# Digits.net
KiCad netlist of a schematic drawn in Altium Designer
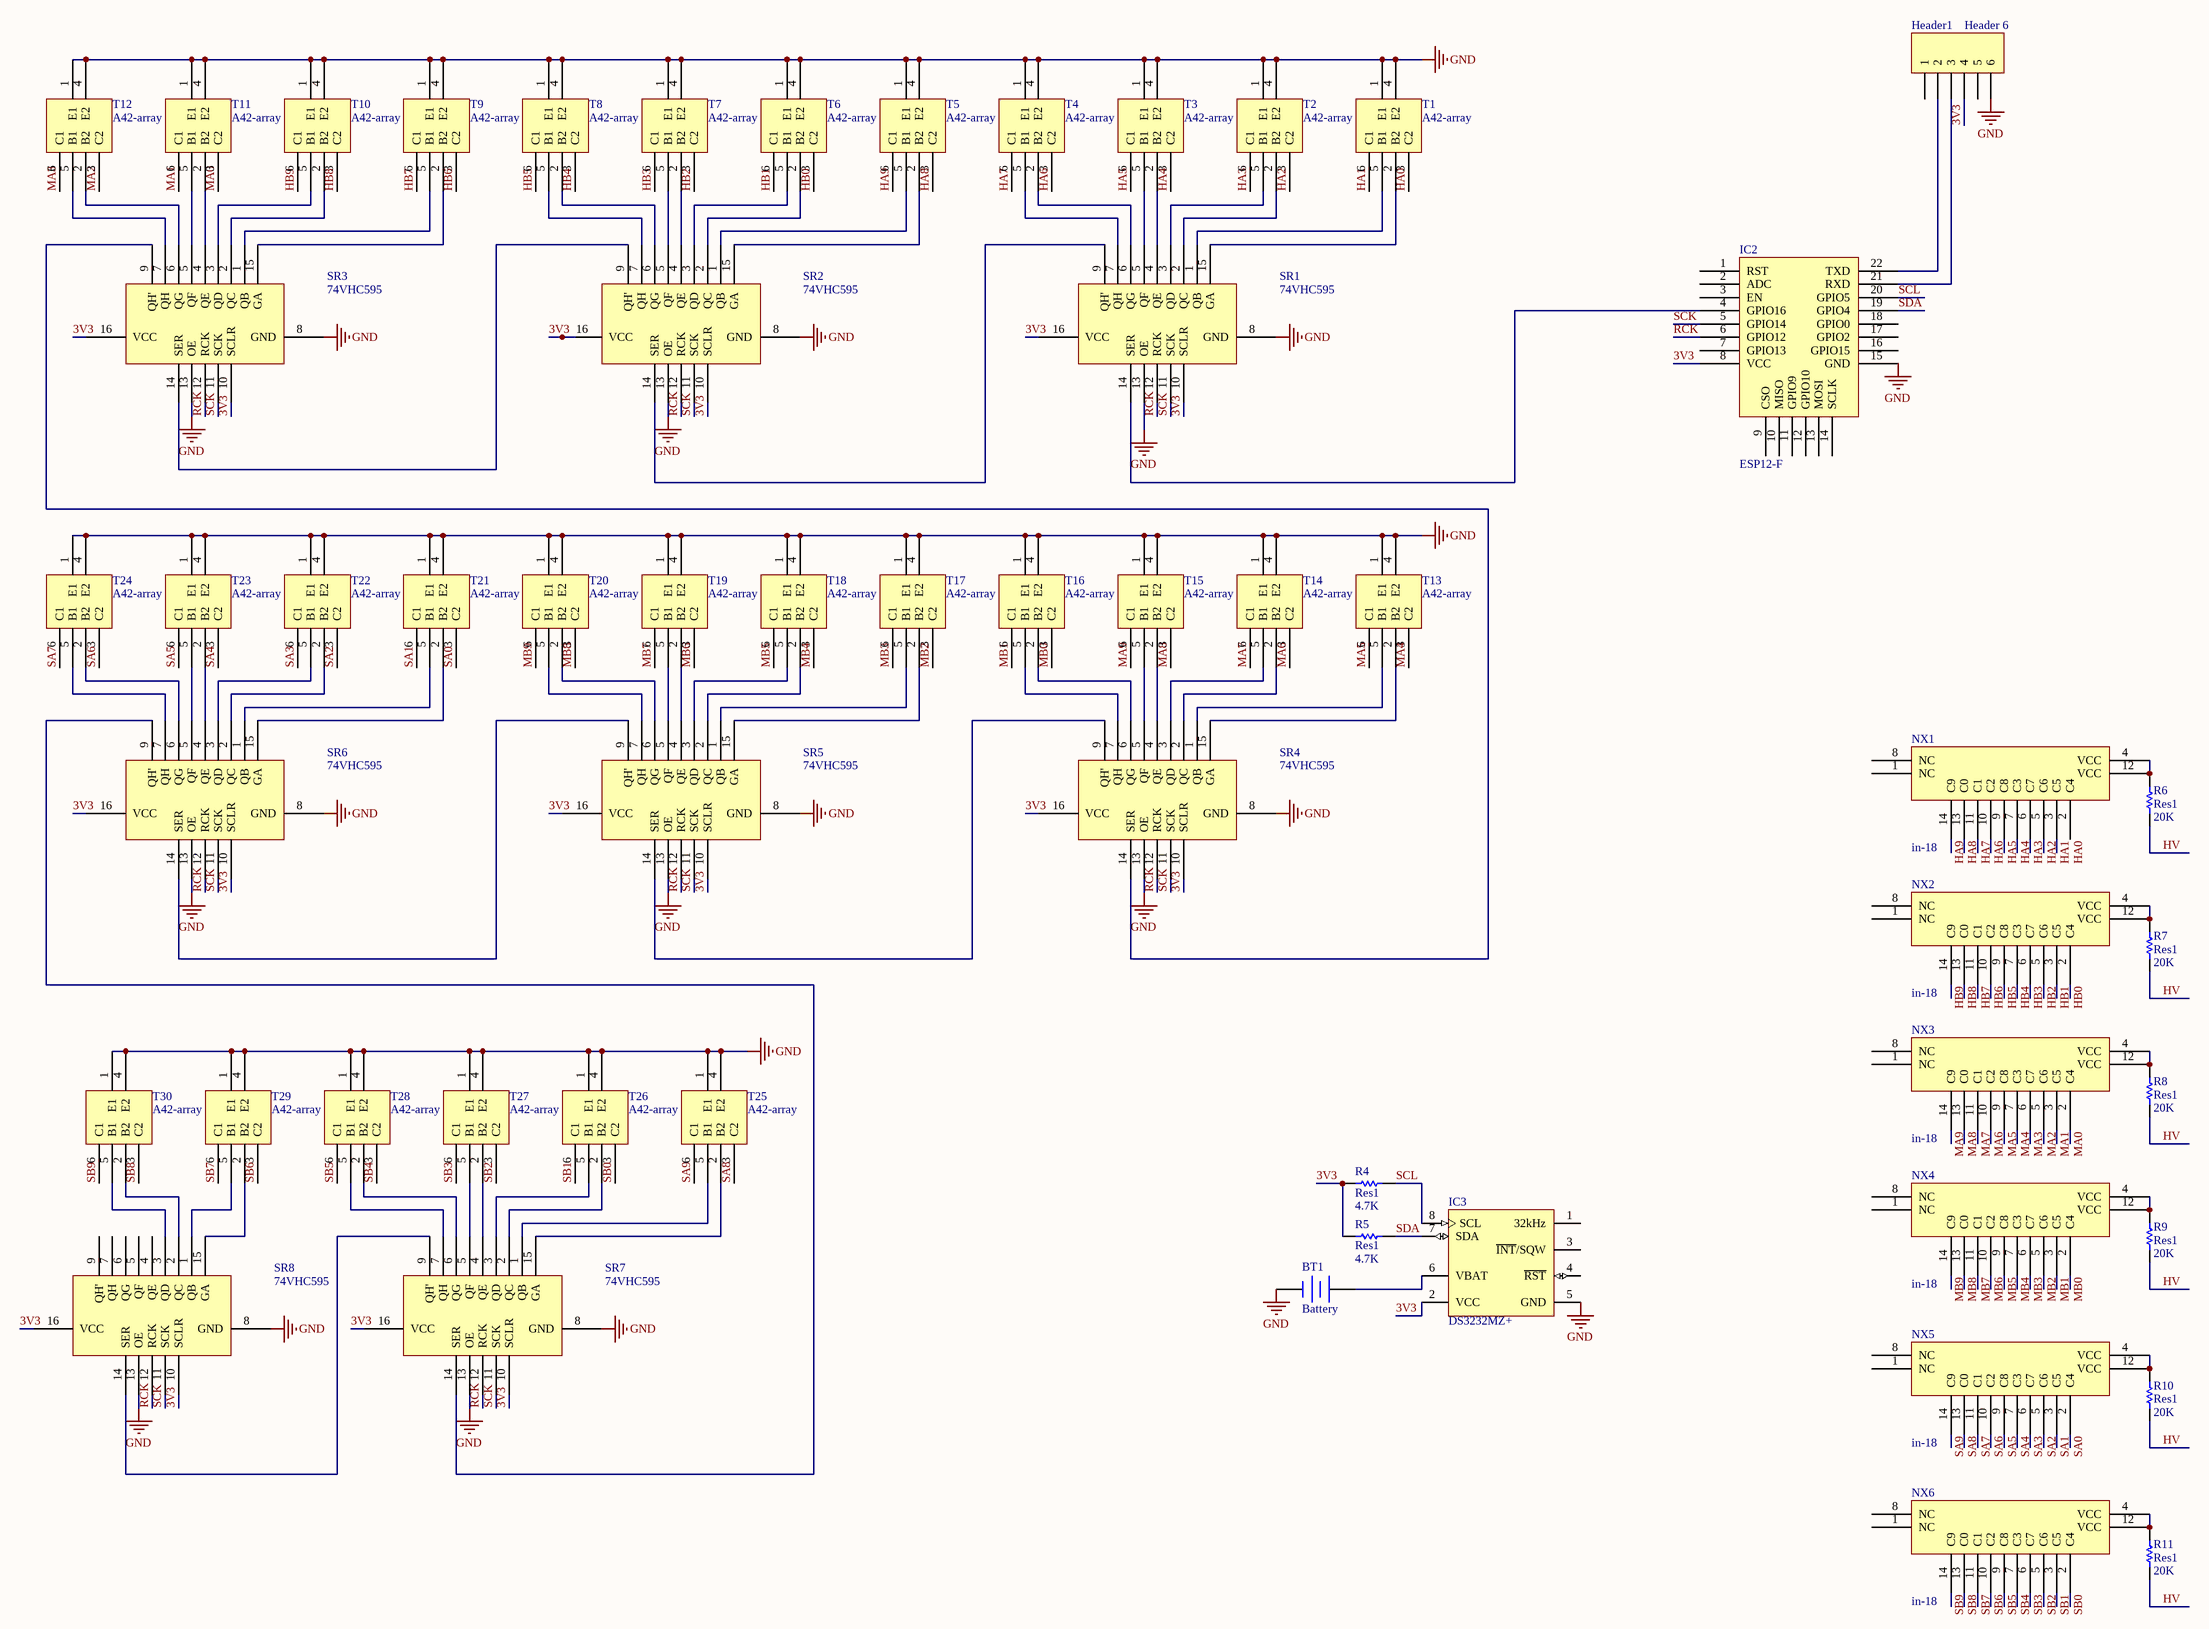
[diagram p0: Digits.SchDoc]

(export (version "E")
  (design (tool "Eeschema 10.0.6"))
  (components
    (comp (ref "BT1")
      (value "Battery")
      (footprint "cr1220")
      (description "Multicell Battery")
      (fields (field (name "PUBLISHER") "Altium Limited"))
      (libsource (lib "Miscellaneous Devices") (part "Battery"))
    )
    (comp (ref "Header1")
      (value "Header 6")
      (footprint "HDR1X6")
      (description "Header, 6-Pin")
      (fields (field (name "PUBLISHER") "Altium Limited"))
      (libsource (lib "Miscellaneous Connectors") (part "Header 6"))
    )
    (comp (ref "IC2")
      (value "ESP12-F")
      (footprint "ESP12-F")
      (libsource (lib "CustomComponentsLibrary") (part "ESP12-F"))
    )
    (comp (ref "IC3")
      (value "DS3232MZ+")
      (footprint "DS3231")
      (libsource (lib "Maxim Real-Time Clocks (RTCs)") (part "DS3232MZ+"))
    )
    (comp (ref "NX1")
      (value "in-18")
      (footprint "in-18")
      (libsource (lib "CustomComponentsLibrary") (part "in-18"))
    )
    (comp (ref "NX2")
      (value "in-18")
      (footprint "in-18")
      (libsource (lib "CustomComponentsLibrary") (part "in-18"))
    )
    (comp (ref "NX3")
      (value "in-18")
      (footprint "in-18")
      (libsource (lib "CustomComponentsLibrary") (part "in-18"))
    )
    (comp (ref "NX4")
      (value "in-18")
      (footprint "in-18")
      (libsource (lib "CustomComponentsLibrary") (part "in-18"))
    )
    (comp (ref "NX5")
      (value "in-18")
      (footprint "in-18")
      (libsource (lib "CustomComponentsLibrary") (part "in-18"))
    )
    (comp (ref "NX6")
      (value "in-18")
      (footprint "in-18")
      (libsource (lib "CustomComponentsLibrary") (part "in-18"))
    )
    (comp (ref "R4")
      (value "Res1")
      (footprint "6-0805_M")
      (description "Resistor")
      (fields (field (name "ALTIUM_VALUE") "4.7K") (field (name "PUBLISHER") "Altium Limited"))
      (libsource (lib "Miscellaneous Devices") (part "Res1"))
    )
    (comp (ref "R5")
      (value "Res1")
      (footprint "6-0805_M")
      (description "Resistor")
      (fields (field (name "ALTIUM_VALUE") "4.7K") (field (name "PUBLISHER") "Altium Limited"))
      (libsource (lib "Miscellaneous Devices") (part "Res1"))
    )
    (comp (ref "R6")
      (value "Res1")
      (footprint "6-0805_M")
      (description "Resistor")
      (fields (field (name "ALTIUM_VALUE") "20K") (field (name "PUBLISHER") "Altium Limited"))
      (libsource (lib "Miscellaneous Devices") (part "Res1"))
    )
    (comp (ref "R7")
      (value "Res1")
      (footprint "6-0805_M")
      (description "Resistor")
      (fields (field (name "ALTIUM_VALUE") "20K") (field (name "PUBLISHER") "Altium Limited"))
      (libsource (lib "Miscellaneous Devices") (part "Res1"))
    )
    (comp (ref "R8")
      (value "Res1")
      (footprint "6-0805_M")
      (description "Resistor")
      (fields (field (name "ALTIUM_VALUE") "20K") (field (name "PUBLISHER") "Altium Limited"))
      (libsource (lib "Miscellaneous Devices") (part "Res1"))
    )
    (comp (ref "R9")
      (value "Res1")
      (footprint "6-0805_M")
      (description "Resistor")
      (fields (field (name "ALTIUM_VALUE") "20K") (field (name "PUBLISHER") "Altium Limited"))
      (libsource (lib "Miscellaneous Devices") (part "Res1"))
    )
    (comp (ref "R10")
      (value "Res1")
      (footprint "6-0805_M")
      (description "Resistor")
      (fields (field (name "ALTIUM_VALUE") "20K") (field (name "PUBLISHER") "Altium Limited"))
      (libsource (lib "Miscellaneous Devices") (part "Res1"))
    )
    (comp (ref "R11")
      (value "Res1")
      (footprint "6-0805_M")
      (description "Resistor")
      (fields (field (name "ALTIUM_VALUE") "20K") (field (name "PUBLISHER") "Altium Limited"))
      (libsource (lib "Miscellaneous Devices") (part "Res1"))
    )
    (comp (ref "SR1")
      (value "74VHC595")
      (footprint "74VHC595")
      (libsource (lib "CustomComponentsLibrary") (part "74VHC595"))
    )
    (comp (ref "SR2")
      (value "74VHC595")
      (footprint "74VHC595")
      (libsource (lib "CustomComponentsLibrary") (part "74VHC595"))
    )
    (comp (ref "SR3")
      (value "74VHC595")
      (footprint "74VHC595")
      (libsource (lib "CustomComponentsLibrary") (part "74VHC595"))
    )
    (comp (ref "SR4")
      (value "74VHC595")
      (footprint "74VHC595")
      (libsource (lib "CustomComponentsLibrary") (part "74VHC595"))
    )
    (comp (ref "SR5")
      (value "74VHC595")
      (footprint "74VHC595")
      (libsource (lib "CustomComponentsLibrary") (part "74VHC595"))
    )
    (comp (ref "SR6")
      (value "74VHC595")
      (footprint "74VHC595")
      (libsource (lib "CustomComponentsLibrary") (part "74VHC595"))
    )
    (comp (ref "SR7")
      (value "74VHC595")
      (footprint "74VHC595")
      (libsource (lib "CustomComponentsLibrary") (part "74VHC595"))
    )
    (comp (ref "SR8")
      (value "74VHC595")
      (footprint "74VHC595")
      (libsource (lib "CustomComponentsLibrary") (part "74VHC595"))
    )
    (comp (ref "T1")
      (value "A42-array")
      (footprint "SOT457")
      (libsource (lib "CustomComponentsLibrary") (part "A42-array"))
    )
    (comp (ref "T2")
      (value "A42-array")
      (footprint "SOT457")
      (libsource (lib "CustomComponentsLibrary") (part "A42-array"))
    )
    (comp (ref "T3")
      (value "A42-array")
      (footprint "SOT457")
      (libsource (lib "CustomComponentsLibrary") (part "A42-array"))
    )
    (comp (ref "T4")
      (value "A42-array")
      (footprint "SOT457")
      (libsource (lib "CustomComponentsLibrary") (part "A42-array"))
    )
    (comp (ref "T5")
      (value "A42-array")
      (footprint "SOT457")
      (libsource (lib "CustomComponentsLibrary") (part "A42-array"))
    )
    (comp (ref "T6")
      (value "A42-array")
      (footprint "SOT457")
      (libsource (lib "CustomComponentsLibrary") (part "A42-array"))
    )
    (comp (ref "T7")
      (value "A42-array")
      (footprint "SOT457")
      (libsource (lib "CustomComponentsLibrary") (part "A42-array"))
    )
    (comp (ref "T8")
      (value "A42-array")
      (footprint "SOT457")
      (libsource (lib "CustomComponentsLibrary") (part "A42-array"))
    )
    (comp (ref "T9")
      (value "A42-array")
      (footprint "SOT457")
      (libsource (lib "CustomComponentsLibrary") (part "A42-array"))
    )
    (comp (ref "T10")
      (value "A42-array")
      (footprint "SOT457")
      (libsource (lib "CustomComponentsLibrary") (part "A42-array"))
    )
    (comp (ref "T11")
      (value "A42-array")
      (footprint "SOT457")
      (libsource (lib "CustomComponentsLibrary") (part "A42-array"))
    )
    (comp (ref "T12")
      (value "A42-array")
      (footprint "SOT457")
      (libsource (lib "CustomComponentsLibrary") (part "A42-array"))
    )
    (comp (ref "T13")
      (value "A42-array")
      (footprint "SOT457")
      (libsource (lib "CustomComponentsLibrary") (part "A42-array"))
    )
    (comp (ref "T14")
      (value "A42-array")
      (footprint "SOT457")
      (libsource (lib "CustomComponentsLibrary") (part "A42-array"))
    )
    (comp (ref "T15")
      (value "A42-array")
      (footprint "SOT457")
      (libsource (lib "CustomComponentsLibrary") (part "A42-array"))
    )
    (comp (ref "T16")
      (value "A42-array")
      (footprint "SOT457")
      (libsource (lib "CustomComponentsLibrary") (part "A42-array"))
    )
    (comp (ref "T17")
      (value "A42-array")
      (footprint "SOT457")
      (libsource (lib "CustomComponentsLibrary") (part "A42-array"))
    )
    (comp (ref "T18")
      (value "A42-array")
      (footprint "SOT457")
      (libsource (lib "CustomComponentsLibrary") (part "A42-array"))
    )
    (comp (ref "T19")
      (value "A42-array")
      (footprint "SOT457")
      (libsource (lib "CustomComponentsLibrary") (part "A42-array"))
    )
    (comp (ref "T20")
      (value "A42-array")
      (footprint "SOT457")
      (libsource (lib "CustomComponentsLibrary") (part "A42-array"))
    )
    (comp (ref "T21")
      (value "A42-array")
      (footprint "SOT457")
      (libsource (lib "CustomComponentsLibrary") (part "A42-array"))
    )
    (comp (ref "T22")
      (value "A42-array")
      (footprint "SOT457")
      (libsource (lib "CustomComponentsLibrary") (part "A42-array"))
    )
    (comp (ref "T23")
      (value "A42-array")
      (footprint "SOT457")
      (libsource (lib "CustomComponentsLibrary") (part "A42-array"))
    )
    (comp (ref "T24")
      (value "A42-array")
      (footprint "SOT457")
      (libsource (lib "CustomComponentsLibrary") (part "A42-array"))
    )
    (comp (ref "T25")
      (value "A42-array")
      (footprint "SOT457")
      (libsource (lib "CustomComponentsLibrary") (part "A42-array"))
    )
    (comp (ref "T26")
      (value "A42-array")
      (footprint "SOT457")
      (libsource (lib "CustomComponentsLibrary") (part "A42-array"))
    )
    (comp (ref "T27")
      (value "A42-array")
      (footprint "SOT457")
      (libsource (lib "CustomComponentsLibrary") (part "A42-array"))
    )
    (comp (ref "T28")
      (value "A42-array")
      (footprint "SOT457")
      (libsource (lib "CustomComponentsLibrary") (part "A42-array"))
    )
    (comp (ref "T29")
      (value "A42-array")
      (footprint "SOT457")
      (libsource (lib "CustomComponentsLibrary") (part "A42-array"))
    )
    (comp (ref "T30")
      (value "A42-array")
      (footprint "SOT457")
      (libsource (lib "CustomComponentsLibrary") (part "A42-array"))
    )
  )
  (nets
    (net (code "1") (name "/3V3") (class "Default")
      (node (ref "Header1") (pin "4") (pinfunction "4_4") (pintype "passive"))
      (node (ref "IC2") (pin "8") (pinfunction "VCC_8") (pintype "passive"))
      (node (ref "IC3") (pin "2") (pinfunction "VCC_2") (pintype "power_in"))
      (node (ref "R4") (pin "2") (pinfunction "2_2") (pintype "passive"))
      (node (ref "R5") (pin "2") (pinfunction "2_2") (pintype "passive"))
      (node (ref "SR1") (pin "10") (pinfunction "SCLR_10") (pintype "passive"))
      (node (ref "SR1") (pin "16") (pinfunction "VCC_16") (pintype "passive"))
      (node (ref "SR2") (pin "10") (pinfunction "SCLR_10") (pintype "passive"))
      (node (ref "SR2") (pin "16") (pinfunction "VCC_16") (pintype "passive"))
      (node (ref "SR3") (pin "10") (pinfunction "SCLR_10") (pintype "passive"))
      (node (ref "SR3") (pin "16") (pinfunction "VCC_16") (pintype "passive"))
      (node (ref "SR4") (pin "10") (pinfunction "SCLR_10") (pintype "passive"))
      (node (ref "SR4") (pin "16") (pinfunction "VCC_16") (pintype "passive"))
      (node (ref "SR5") (pin "10") (pinfunction "SCLR_10") (pintype "passive"))
      (node (ref "SR5") (pin "16") (pinfunction "VCC_16") (pintype "passive"))
      (node (ref "SR6") (pin "10") (pinfunction "SCLR_10") (pintype "passive"))
      (node (ref "SR6") (pin "16") (pinfunction "VCC_16") (pintype "passive"))
      (node (ref "SR7") (pin "10") (pinfunction "SCLR_10") (pintype "passive"))
      (node (ref "SR7") (pin "16") (pinfunction "VCC_16") (pintype "passive"))
      (node (ref "SR8") (pin "10") (pinfunction "SCLR_10") (pintype "passive"))
      (node (ref "SR8") (pin "16") (pinfunction "VCC_16") (pintype "passive"))
    )
    (net (code "2") (name "/HA0") (class "Default")
      (node (ref "NX1") (pin "2") (pinfunction "C4_2") (pintype "passive"))
      (node (ref "T1") (pin "3") (pinfunction "C2_3") (pintype "passive"))
    )
    (net (code "3") (name "/HA1") (class "Default")
      (node (ref "NX1") (pin "3") (pinfunction "C5_3") (pintype "passive"))
      (node (ref "T1") (pin "6") (pinfunction "C1_6") (pintype "passive"))
    )
    (net (code "4") (name "/HA2") (class "Default")
      (node (ref "NX1") (pin "5") (pinfunction "C6_5") (pintype "passive"))
      (node (ref "T2") (pin "3") (pinfunction "C2_3") (pintype "passive"))
    )
    (net (code "5") (name "/HA3") (class "Default")
      (node (ref "NX1") (pin "6") (pinfunction "C7_6") (pintype "passive"))
      (node (ref "T2") (pin "6") (pinfunction "C1_6") (pintype "passive"))
    )
    (net (code "6") (name "/HA4") (class "Default")
      (node (ref "NX1") (pin "7") (pinfunction "C3_7") (pintype "passive"))
      (node (ref "T3") (pin "3") (pinfunction "C2_3") (pintype "passive"))
    )
    (net (code "7") (name "/HA5") (class "Default")
      (node (ref "NX1") (pin "9") (pinfunction "C8_9") (pintype "passive"))
      (node (ref "T3") (pin "6") (pinfunction "C1_6") (pintype "passive"))
    )
    (net (code "8") (name "/HA6") (class "Default")
      (node (ref "NX1") (pin "10") (pinfunction "C2_10") (pintype "passive"))
      (node (ref "T4") (pin "3") (pinfunction "C2_3") (pintype "passive"))
    )
    (net (code "9") (name "/HA7") (class "Default")
      (node (ref "NX1") (pin "11") (pinfunction "C1_11") (pintype "passive"))
      (node (ref "T4") (pin "6") (pinfunction "C1_6") (pintype "passive"))
    )
    (net (code "10") (name "/HA8") (class "Default")
      (node (ref "NX1") (pin "13") (pinfunction "C0_13") (pintype "passive"))
      (node (ref "T5") (pin "3") (pinfunction "C2_3") (pintype "passive"))
    )
    (net (code "11") (name "/HA9") (class "Default")
      (node (ref "NX1") (pin "14") (pinfunction "C9_14") (pintype "passive"))
      (node (ref "T5") (pin "6") (pinfunction "C1_6") (pintype "passive"))
    )
    (net (code "12") (name "/HB0") (class "Default")
      (node (ref "NX2") (pin "2") (pinfunction "C4_2") (pintype "passive"))
      (node (ref "T6") (pin "3") (pinfunction "C2_3") (pintype "passive"))
    )
    (net (code "13") (name "/HB1") (class "Default")
      (node (ref "NX2") (pin "3") (pinfunction "C5_3") (pintype "passive"))
      (node (ref "T6") (pin "6") (pinfunction "C1_6") (pintype "passive"))
    )
    (net (code "14") (name "/HB2") (class "Default")
      (node (ref "NX2") (pin "5") (pinfunction "C6_5") (pintype "passive"))
      (node (ref "T7") (pin "3") (pinfunction "C2_3") (pintype "passive"))
    )
    (net (code "15") (name "/HB3") (class "Default")
      (node (ref "NX2") (pin "6") (pinfunction "C7_6") (pintype "passive"))
      (node (ref "T7") (pin "6") (pinfunction "C1_6") (pintype "passive"))
    )
    (net (code "16") (name "/HB4") (class "Default")
      (node (ref "NX2") (pin "7") (pinfunction "C3_7") (pintype "passive"))
      (node (ref "T8") (pin "3") (pinfunction "C2_3") (pintype "passive"))
    )
    (net (code "17") (name "/HB5") (class "Default")
      (node (ref "NX2") (pin "9") (pinfunction "C8_9") (pintype "passive"))
      (node (ref "T8") (pin "6") (pinfunction "C1_6") (pintype "passive"))
    )
    (net (code "18") (name "/HB6") (class "Default")
      (node (ref "NX2") (pin "10") (pinfunction "C2_10") (pintype "passive"))
      (node (ref "T9") (pin "3") (pinfunction "C2_3") (pintype "passive"))
    )
    (net (code "19") (name "/HB7") (class "Default")
      (node (ref "NX2") (pin "11") (pinfunction "C1_11") (pintype "passive"))
      (node (ref "T9") (pin "6") (pinfunction "C1_6") (pintype "passive"))
    )
    (net (code "20") (name "/HB8") (class "Default")
      (node (ref "NX2") (pin "13") (pinfunction "C0_13") (pintype "passive"))
      (node (ref "T10") (pin "3") (pinfunction "C2_3") (pintype "passive"))
    )
    (net (code "21") (name "/HB9") (class "Default")
      (node (ref "NX2") (pin "14") (pinfunction "C9_14") (pintype "passive"))
      (node (ref "T10") (pin "6") (pinfunction "C1_6") (pintype "passive"))
    )
    (net (code "22") (name "/HV") (class "Default")
      (node (ref "R10") (pin "1") (pinfunction "1_1") (pintype "passive"))
      (node (ref "R11") (pin "1") (pinfunction "1_1") (pintype "passive"))
      (node (ref "R6") (pin "1") (pinfunction "1_1") (pintype "passive"))
      (node (ref "R7") (pin "1") (pinfunction "1_1") (pintype "passive"))
      (node (ref "R8") (pin "1") (pinfunction "1_1") (pintype "passive"))
      (node (ref "R9") (pin "1") (pinfunction "1_1") (pintype "passive"))
    )
    (net (code "23") (name "/MA0") (class "Default")
      (node (ref "NX3") (pin "2") (pinfunction "C4_2") (pintype "passive"))
      (node (ref "T11") (pin "3") (pinfunction "C2_3") (pintype "passive"))
    )
    (net (code "24") (name "/MA1") (class "Default")
      (node (ref "NX3") (pin "3") (pinfunction "C5_3") (pintype "passive"))
      (node (ref "T11") (pin "6") (pinfunction "C1_6") (pintype "passive"))
    )
    (net (code "25") (name "/MA2") (class "Default")
      (node (ref "NX3") (pin "5") (pinfunction "C6_5") (pintype "passive"))
      (node (ref "T12") (pin "3") (pinfunction "C2_3") (pintype "passive"))
    )
    (net (code "26") (name "/MA3") (class "Default")
      (node (ref "NX3") (pin "6") (pinfunction "C7_6") (pintype "passive"))
      (node (ref "T12") (pin "6") (pinfunction "C1_6") (pintype "passive"))
    )
    (net (code "27") (name "/MA4") (class "Default")
      (node (ref "NX3") (pin "7") (pinfunction "C3_7") (pintype "passive"))
      (node (ref "T13") (pin "3") (pinfunction "C2_3") (pintype "passive"))
    )
    (net (code "28") (name "/MA5") (class "Default")
      (node (ref "NX3") (pin "9") (pinfunction "C8_9") (pintype "passive"))
      (node (ref "T13") (pin "6") (pinfunction "C1_6") (pintype "passive"))
    )
    (net (code "29") (name "/MA6") (class "Default")
      (node (ref "NX3") (pin "10") (pinfunction "C2_10") (pintype "passive"))
      (node (ref "T14") (pin "3") (pinfunction "C2_3") (pintype "passive"))
    )
    (net (code "30") (name "/MA7") (class "Default")
      (node (ref "NX3") (pin "11") (pinfunction "C1_11") (pintype "passive"))
      (node (ref "T14") (pin "6") (pinfunction "C1_6") (pintype "passive"))
    )
    (net (code "31") (name "/MA8") (class "Default")
      (node (ref "NX3") (pin "13") (pinfunction "C0_13") (pintype "passive"))
      (node (ref "T15") (pin "3") (pinfunction "C2_3") (pintype "passive"))
    )
    (net (code "32") (name "/MA9") (class "Default")
      (node (ref "NX3") (pin "14") (pinfunction "C9_14") (pintype "passive"))
      (node (ref "T15") (pin "6") (pinfunction "C1_6") (pintype "passive"))
    )
    (net (code "33") (name "/MB0") (class "Default")
      (node (ref "NX4") (pin "2") (pinfunction "C4_2") (pintype "passive"))
      (node (ref "T16") (pin "3") (pinfunction "C2_3") (pintype "passive"))
    )
    (net (code "34") (name "/MB1") (class "Default")
      (node (ref "NX4") (pin "3") (pinfunction "C5_3") (pintype "passive"))
      (node (ref "T16") (pin "6") (pinfunction "C1_6") (pintype "passive"))
    )
    (net (code "35") (name "/MB2") (class "Default")
      (node (ref "NX4") (pin "5") (pinfunction "C6_5") (pintype "passive"))
      (node (ref "T17") (pin "3") (pinfunction "C2_3") (pintype "passive"))
    )
    (net (code "36") (name "/MB3") (class "Default")
      (node (ref "NX4") (pin "6") (pinfunction "C7_6") (pintype "passive"))
      (node (ref "T17") (pin "6") (pinfunction "C1_6") (pintype "passive"))
    )
    (net (code "37") (name "/MB4") (class "Default")
      (node (ref "NX4") (pin "7") (pinfunction "C3_7") (pintype "passive"))
      (node (ref "T18") (pin "3") (pinfunction "C2_3") (pintype "passive"))
    )
    (net (code "38") (name "/MB5") (class "Default")
      (node (ref "NX4") (pin "9") (pinfunction "C8_9") (pintype "passive"))
      (node (ref "T18") (pin "6") (pinfunction "C1_6") (pintype "passive"))
    )
    (net (code "39") (name "/MB6") (class "Default")
      (node (ref "NX4") (pin "10") (pinfunction "C2_10") (pintype "passive"))
      (node (ref "T19") (pin "3") (pinfunction "C2_3") (pintype "passive"))
    )
    (net (code "40") (name "/MB7") (class "Default")
      (node (ref "NX4") (pin "11") (pinfunction "C1_11") (pintype "passive"))
      (node (ref "T19") (pin "6") (pinfunction "C1_6") (pintype "passive"))
    )
    (net (code "41") (name "/MB8") (class "Default")
      (node (ref "NX4") (pin "13") (pinfunction "C0_13") (pintype "passive"))
      (node (ref "T20") (pin "3") (pinfunction "C2_3") (pintype "passive"))
    )
    (net (code "42") (name "/MB9") (class "Default")
      (node (ref "NX4") (pin "14") (pinfunction "C9_14") (pintype "passive"))
      (node (ref "T20") (pin "6") (pinfunction "C1_6") (pintype "passive"))
    )
    (net (code "43") (name "/RCK") (class "Default")
      (node (ref "IC2") (pin "6") (pinfunction "GPIO12_6") (pintype "passive"))
      (node (ref "SR1") (pin "12") (pinfunction "RCK_12") (pintype "passive"))
      (node (ref "SR2") (pin "12") (pinfunction "RCK_12") (pintype "passive"))
      (node (ref "SR3") (pin "12") (pinfunction "RCK_12") (pintype "passive"))
      (node (ref "SR4") (pin "12") (pinfunction "RCK_12") (pintype "passive"))
      (node (ref "SR5") (pin "12") (pinfunction "RCK_12") (pintype "passive"))
      (node (ref "SR6") (pin "12") (pinfunction "RCK_12") (pintype "passive"))
      (node (ref "SR7") (pin "12") (pinfunction "RCK_12") (pintype "passive"))
      (node (ref "SR8") (pin "12") (pinfunction "RCK_12") (pintype "passive"))
    )
    (net (code "44") (name "/SA0") (class "Default")
      (node (ref "NX5") (pin "2") (pinfunction "C4_2") (pintype "passive"))
      (node (ref "T21") (pin "3") (pinfunction "C2_3") (pintype "passive"))
    )
    (net (code "45") (name "/SA1") (class "Default")
      (node (ref "NX5") (pin "3") (pinfunction "C5_3") (pintype "passive"))
      (node (ref "T21") (pin "6") (pinfunction "C1_6") (pintype "passive"))
    )
    (net (code "46") (name "/SA2") (class "Default")
      (node (ref "NX5") (pin "5") (pinfunction "C6_5") (pintype "passive"))
      (node (ref "T22") (pin "3") (pinfunction "C2_3") (pintype "passive"))
    )
    (net (code "47") (name "/SA3") (class "Default")
      (node (ref "NX5") (pin "6") (pinfunction "C7_6") (pintype "passive"))
      (node (ref "T22") (pin "6") (pinfunction "C1_6") (pintype "passive"))
    )
    (net (code "48") (name "/SA4") (class "Default")
      (node (ref "NX5") (pin "7") (pinfunction "C3_7") (pintype "passive"))
      (node (ref "T23") (pin "3") (pinfunction "C2_3") (pintype "passive"))
    )
    (net (code "49") (name "/SA5") (class "Default")
      (node (ref "NX5") (pin "9") (pinfunction "C8_9") (pintype "passive"))
      (node (ref "T23") (pin "6") (pinfunction "C1_6") (pintype "passive"))
    )
    (net (code "50") (name "/SA6") (class "Default")
      (node (ref "NX5") (pin "10") (pinfunction "C2_10") (pintype "passive"))
      (node (ref "T24") (pin "3") (pinfunction "C2_3") (pintype "passive"))
    )
    (net (code "51") (name "/SA7") (class "Default")
      (node (ref "NX5") (pin "11") (pinfunction "C1_11") (pintype "passive"))
      (node (ref "T24") (pin "6") (pinfunction "C1_6") (pintype "passive"))
    )
    (net (code "52") (name "/SA8") (class "Default")
      (node (ref "NX5") (pin "13") (pinfunction "C0_13") (pintype "passive"))
      (node (ref "T25") (pin "3") (pinfunction "C2_3") (pintype "passive"))
    )
    (net (code "53") (name "/SA9") (class "Default")
      (node (ref "NX5") (pin "14") (pinfunction "C9_14") (pintype "passive"))
      (node (ref "T25") (pin "6") (pinfunction "C1_6") (pintype "passive"))
    )
    (net (code "54") (name "/SB0") (class "Default")
      (node (ref "NX6") (pin "2") (pinfunction "C4_2") (pintype "passive"))
      (node (ref "T26") (pin "3") (pinfunction "C2_3") (pintype "passive"))
    )
    (net (code "55") (name "/SB1") (class "Default")
      (node (ref "NX6") (pin "3") (pinfunction "C5_3") (pintype "passive"))
      (node (ref "T26") (pin "6") (pinfunction "C1_6") (pintype "passive"))
    )
    (net (code "56") (name "/SB2") (class "Default")
      (node (ref "NX6") (pin "5") (pinfunction "C6_5") (pintype "passive"))
      (node (ref "T27") (pin "3") (pinfunction "C2_3") (pintype "passive"))
    )
    (net (code "57") (name "/SB3") (class "Default")
      (node (ref "NX6") (pin "6") (pinfunction "C7_6") (pintype "passive"))
      (node (ref "T27") (pin "6") (pinfunction "C1_6") (pintype "passive"))
    )
    (net (code "58") (name "/SB4") (class "Default")
      (node (ref "NX6") (pin "7") (pinfunction "C3_7") (pintype "passive"))
      (node (ref "T28") (pin "3") (pinfunction "C2_3") (pintype "passive"))
    )
    (net (code "59") (name "/SB5") (class "Default")
      (node (ref "NX6") (pin "9") (pinfunction "C8_9") (pintype "passive"))
      (node (ref "T28") (pin "6") (pinfunction "C1_6") (pintype "passive"))
    )
    (net (code "60") (name "/SB6") (class "Default")
      (node (ref "NX6") (pin "10") (pinfunction "C2_10") (pintype "passive"))
      (node (ref "T29") (pin "3") (pinfunction "C2_3") (pintype "passive"))
    )
    (net (code "61") (name "/SB7") (class "Default")
      (node (ref "NX6") (pin "11") (pinfunction "C1_11") (pintype "passive"))
      (node (ref "T29") (pin "6") (pinfunction "C1_6") (pintype "passive"))
    )
    (net (code "62") (name "/SB8") (class "Default")
      (node (ref "NX6") (pin "13") (pinfunction "C0_13") (pintype "passive"))
      (node (ref "T30") (pin "3") (pinfunction "C2_3") (pintype "passive"))
    )
    (net (code "63") (name "/SB9") (class "Default")
      (node (ref "NX6") (pin "14") (pinfunction "C9_14") (pintype "passive"))
      (node (ref "T30") (pin "6") (pinfunction "C1_6") (pintype "passive"))
    )
    (net (code "64") (name "/SCK") (class "Default")
      (node (ref "IC2") (pin "5") (pinfunction "GPIO14_5") (pintype "passive"))
      (node (ref "SR1") (pin "11") (pinfunction "SCK_11") (pintype "passive"))
      (node (ref "SR2") (pin "11") (pinfunction "SCK_11") (pintype "passive"))
      (node (ref "SR3") (pin "11") (pinfunction "SCK_11") (pintype "passive"))
      (node (ref "SR4") (pin "11") (pinfunction "SCK_11") (pintype "passive"))
      (node (ref "SR5") (pin "11") (pinfunction "SCK_11") (pintype "passive"))
      (node (ref "SR6") (pin "11") (pinfunction "SCK_11") (pintype "passive"))
      (node (ref "SR7") (pin "11") (pinfunction "SCK_11") (pintype "passive"))
      (node (ref "SR8") (pin "11") (pinfunction "SCK_11") (pintype "passive"))
    )
    (net (code "65") (name "/SCL") (class "Default")
      (node (ref "IC2") (pin "20") (pinfunction "GPIO5_20") (pintype "passive"))
      (node (ref "IC3") (pin "8") (pinfunction "SCL_8") (pintype "input"))
      (node (ref "R4") (pin "1") (pinfunction "1_1") (pintype "passive"))
    )
    (net (code "66") (name "/SDA") (class "Default")
      (node (ref "IC2") (pin "19") (pinfunction "GPIO4_19") (pintype "passive"))
      (node (ref "IC3") (pin "7") (pinfunction "SDA_7") (pintype "bidirectional"))
      (node (ref "R5") (pin "1") (pinfunction "1_1") (pintype "passive"))
    )
    (net (code "67") (name "GND") (class "Default")
      (node (ref "BT1") (pin "2") (pinfunction "-_2") (pintype "passive"))
      (node (ref "Header1") (pin "6") (pinfunction "6_6") (pintype "passive"))
      (node (ref "IC2") (pin "15") (pinfunction "GND_15") (pintype "passive"))
      (node (ref "IC3") (pin "5") (pinfunction "GND_5") (pintype "power_in"))
      (node (ref "SR1") (pin "13") (pinfunction "OE_13") (pintype "passive"))
      (node (ref "SR1") (pin "8") (pinfunction "GND_8") (pintype "passive"))
      (node (ref "SR2") (pin "13") (pinfunction "OE_13") (pintype "passive"))
      (node (ref "SR2") (pin "8") (pinfunction "GND_8") (pintype "passive"))
      (node (ref "SR3") (pin "13") (pinfunction "OE_13") (pintype "passive"))
      (node (ref "SR3") (pin "8") (pinfunction "GND_8") (pintype "passive"))
      (node (ref "SR4") (pin "13") (pinfunction "OE_13") (pintype "passive"))
      (node (ref "SR4") (pin "8") (pinfunction "GND_8") (pintype "passive"))
      (node (ref "SR5") (pin "13") (pinfunction "OE_13") (pintype "passive"))
      (node (ref "SR5") (pin "8") (pinfunction "GND_8") (pintype "passive"))
      (node (ref "SR6") (pin "13") (pinfunction "OE_13") (pintype "passive"))
      (node (ref "SR6") (pin "8") (pinfunction "GND_8") (pintype "passive"))
      (node (ref "SR7") (pin "13") (pinfunction "OE_13") (pintype "passive"))
      (node (ref "SR7") (pin "8") (pinfunction "GND_8") (pintype "passive"))
      (node (ref "SR8") (pin "13") (pinfunction "OE_13") (pintype "passive"))
      (node (ref "SR8") (pin "8") (pinfunction "GND_8") (pintype "passive"))
      (node (ref "T1") (pin "1") (pinfunction "E1_1") (pintype "passive"))
      (node (ref "T1") (pin "4") (pinfunction "E2_4") (pintype "passive"))
      (node (ref "T10") (pin "1") (pinfunction "E1_1") (pintype "passive"))
      (node (ref "T10") (pin "4") (pinfunction "E2_4") (pintype "passive"))
      (node (ref "T11") (pin "1") (pinfunction "E1_1") (pintype "passive"))
      (node (ref "T11") (pin "4") (pinfunction "E2_4") (pintype "passive"))
      (node (ref "T12") (pin "1") (pinfunction "E1_1") (pintype "passive"))
      (node (ref "T12") (pin "4") (pinfunction "E2_4") (pintype "passive"))
      (node (ref "T13") (pin "1") (pinfunction "E1_1") (pintype "passive"))
      (node (ref "T13") (pin "4") (pinfunction "E2_4") (pintype "passive"))
      (node (ref "T14") (pin "1") (pinfunction "E1_1") (pintype "passive"))
      (node (ref "T14") (pin "4") (pinfunction "E2_4") (pintype "passive"))
      (node (ref "T15") (pin "1") (pinfunction "E1_1") (pintype "passive"))
      (node (ref "T15") (pin "4") (pinfunction "E2_4") (pintype "passive"))
      (node (ref "T16") (pin "1") (pinfunction "E1_1") (pintype "passive"))
      (node (ref "T16") (pin "4") (pinfunction "E2_4") (pintype "passive"))
      (node (ref "T17") (pin "1") (pinfunction "E1_1") (pintype "passive"))
      (node (ref "T17") (pin "4") (pinfunction "E2_4") (pintype "passive"))
      (node (ref "T18") (pin "1") (pinfunction "E1_1") (pintype "passive"))
      (node (ref "T18") (pin "4") (pinfunction "E2_4") (pintype "passive"))
      (node (ref "T19") (pin "1") (pinfunction "E1_1") (pintype "passive"))
      (node (ref "T19") (pin "4") (pinfunction "E2_4") (pintype "passive"))
      (node (ref "T2") (pin "1") (pinfunction "E1_1") (pintype "passive"))
      (node (ref "T2") (pin "4") (pinfunction "E2_4") (pintype "passive"))
      (node (ref "T20") (pin "1") (pinfunction "E1_1") (pintype "passive"))
      (node (ref "T20") (pin "4") (pinfunction "E2_4") (pintype "passive"))
      (node (ref "T21") (pin "1") (pinfunction "E1_1") (pintype "passive"))
      (node (ref "T21") (pin "4") (pinfunction "E2_4") (pintype "passive"))
      (node (ref "T22") (pin "1") (pinfunction "E1_1") (pintype "passive"))
      (node (ref "T22") (pin "4") (pinfunction "E2_4") (pintype "passive"))
      (node (ref "T23") (pin "1") (pinfunction "E1_1") (pintype "passive"))
      (node (ref "T23") (pin "4") (pinfunction "E2_4") (pintype "passive"))
      (node (ref "T24") (pin "1") (pinfunction "E1_1") (pintype "passive"))
      (node (ref "T24") (pin "4") (pinfunction "E2_4") (pintype "passive"))
      (node (ref "T25") (pin "1") (pinfunction "E1_1") (pintype "passive"))
      (node (ref "T25") (pin "4") (pinfunction "E2_4") (pintype "passive"))
      (node (ref "T26") (pin "1") (pinfunction "E1_1") (pintype "passive"))
      (node (ref "T26") (pin "4") (pinfunction "E2_4") (pintype "passive"))
      (node (ref "T27") (pin "1") (pinfunction "E1_1") (pintype "passive"))
      (node (ref "T27") (pin "4") (pinfunction "E2_4") (pintype "passive"))
      (node (ref "T28") (pin "1") (pinfunction "E1_1") (pintype "passive"))
      (node (ref "T28") (pin "4") (pinfunction "E2_4") (pintype "passive"))
      (node (ref "T29") (pin "1") (pinfunction "E1_1") (pintype "passive"))
      (node (ref "T29") (pin "4") (pinfunction "E2_4") (pintype "passive"))
      (node (ref "T3") (pin "1") (pinfunction "E1_1") (pintype "passive"))
      (node (ref "T3") (pin "4") (pinfunction "E2_4") (pintype "passive"))
      (node (ref "T30") (pin "1") (pinfunction "E1_1") (pintype "passive"))
      (node (ref "T30") (pin "4") (pinfunction "E2_4") (pintype "passive"))
      (node (ref "T4") (pin "1") (pinfunction "E1_1") (pintype "passive"))
      (node (ref "T4") (pin "4") (pinfunction "E2_4") (pintype "passive"))
      (node (ref "T5") (pin "1") (pinfunction "E1_1") (pintype "passive"))
      (node (ref "T5") (pin "4") (pinfunction "E2_4") (pintype "passive"))
      (node (ref "T6") (pin "1") (pinfunction "E1_1") (pintype "passive"))
      (node (ref "T6") (pin "4") (pinfunction "E2_4") (pintype "passive"))
      (node (ref "T7") (pin "1") (pinfunction "E1_1") (pintype "passive"))
      (node (ref "T7") (pin "4") (pinfunction "E2_4") (pintype "passive"))
      (node (ref "T8") (pin "1") (pinfunction "E1_1") (pintype "passive"))
      (node (ref "T8") (pin "4") (pinfunction "E2_4") (pintype "passive"))
      (node (ref "T9") (pin "1") (pinfunction "E1_1") (pintype "passive"))
      (node (ref "T9") (pin "4") (pinfunction "E2_4") (pintype "passive"))
    )
    (net (code "68") (name "Net-(BT1-+)") (class "Default")
      (node (ref "BT1") (pin "1") (pinfunction "+_1") (pintype "passive"))
      (node (ref "IC3") (pin "6") (pinfunction "VBAT_6") (pintype "power_in"))
    )
    (net (code "69") (name "Net-(IC2-GPIO16)") (class "Default")
      (node (ref "IC2") (pin "4") (pinfunction "GPIO16_4") (pintype "passive"))
      (node (ref "SR1") (pin "14") (pinfunction "SER_14") (pintype "passive"))
    )
    (net (code "70") (name "Net-(IC2-RXD)") (class "Default")
      (node (ref "Header1") (pin "3") (pinfunction "3_3") (pintype "passive"))
      (node (ref "IC2") (pin "21") (pinfunction "RXD_21") (pintype "passive"))
    )
    (net (code "71") (name "Net-(IC2-TXD)") (class "Default")
      (node (ref "Header1") (pin "2") (pinfunction "2_2") (pintype "passive"))
      (node (ref "IC2") (pin "22") (pinfunction "TXD_22") (pintype "passive"))
    )
    (net (code "72") (name "Net-(NX1-VCC-Pad12)") (class "Default")
      (node (ref "NX1") (pin "12") (pinfunction "VCC_12") (pintype "passive"))
      (node (ref "NX1") (pin "4") (pinfunction "VCC_4") (pintype "passive"))
      (node (ref "R6") (pin "2") (pinfunction "2_2") (pintype "passive"))
    )
    (net (code "73") (name "Net-(NX2-VCC-Pad12)") (class "Default")
      (node (ref "NX2") (pin "12") (pinfunction "VCC_12") (pintype "passive"))
      (node (ref "NX2") (pin "4") (pinfunction "VCC_4") (pintype "passive"))
      (node (ref "R7") (pin "2") (pinfunction "2_2") (pintype "passive"))
    )
    (net (code "74") (name "Net-(NX3-VCC-Pad12)") (class "Default")
      (node (ref "NX3") (pin "12") (pinfunction "VCC_12") (pintype "passive"))
      (node (ref "NX3") (pin "4") (pinfunction "VCC_4") (pintype "passive"))
      (node (ref "R8") (pin "2") (pinfunction "2_2") (pintype "passive"))
    )
    (net (code "75") (name "Net-(NX4-VCC-Pad12)") (class "Default")
      (node (ref "NX4") (pin "12") (pinfunction "VCC_12") (pintype "passive"))
      (node (ref "NX4") (pin "4") (pinfunction "VCC_4") (pintype "passive"))
      (node (ref "R9") (pin "2") (pinfunction "2_2") (pintype "passive"))
    )
    (net (code "76") (name "Net-(NX5-VCC-Pad12)") (class "Default")
      (node (ref "NX5") (pin "12") (pinfunction "VCC_12") (pintype "passive"))
      (node (ref "NX5") (pin "4") (pinfunction "VCC_4") (pintype "passive"))
      (node (ref "R10") (pin "2") (pinfunction "2_2") (pintype "passive"))
    )
    (net (code "77") (name "Net-(NX6-VCC-Pad12)") (class "Default")
      (node (ref "NX6") (pin "12") (pinfunction "VCC_12") (pintype "passive"))
      (node (ref "NX6") (pin "4") (pinfunction "VCC_4") (pintype "passive"))
      (node (ref "R11") (pin "2") (pinfunction "2_2") (pintype "passive"))
    )
    (net (code "78") (name "Net-(SR1-GA)") (class "Default")
      (node (ref "SR1") (pin "15") (pinfunction "GA_15") (pintype "passive"))
      (node (ref "T1") (pin "2") (pinfunction "B2_2") (pintype "passive"))
    )
    (net (code "79") (name "Net-(SR1-QB)") (class "Default")
      (node (ref "SR1") (pin "1") (pinfunction "QB_1") (pintype "passive"))
      (node (ref "T1") (pin "5") (pinfunction "B1_5") (pintype "passive"))
    )
    (net (code "80") (name "Net-(SR1-QC)") (class "Default")
      (node (ref "SR1") (pin "2") (pinfunction "QC_2") (pintype "passive"))
      (node (ref "T2") (pin "2") (pinfunction "B2_2") (pintype "passive"))
    )
    (net (code "81") (name "Net-(SR1-QD)") (class "Default")
      (node (ref "SR1") (pin "3") (pinfunction "QD_3") (pintype "passive"))
      (node (ref "T2") (pin "5") (pinfunction "B1_5") (pintype "passive"))
    )
    (net (code "82") (name "Net-(SR1-QE)") (class "Default")
      (node (ref "SR1") (pin "4") (pinfunction "QE_4") (pintype "passive"))
      (node (ref "T3") (pin "2") (pinfunction "B2_2") (pintype "passive"))
    )
    (net (code "83") (name "Net-(SR1-QF)") (class "Default")
      (node (ref "SR1") (pin "5") (pinfunction "QF_5") (pintype "passive"))
      (node (ref "T3") (pin "5") (pinfunction "B1_5") (pintype "passive"))
    )
    (net (code "84") (name "Net-(SR1-QG)") (class "Default")
      (node (ref "SR1") (pin "6") (pinfunction "QG_6") (pintype "passive"))
      (node (ref "T4") (pin "2") (pinfunction "B2_2") (pintype "passive"))
    )
    (net (code "85") (name "Net-(SR1-QH')") (class "Default")
      (node (ref "SR1") (pin "9") (pinfunction "QH'_9") (pintype "passive"))
      (node (ref "SR2") (pin "14") (pinfunction "SER_14") (pintype "passive"))
    )
    (net (code "86") (name "Net-(SR1-QH)") (class "Default")
      (node (ref "SR1") (pin "7") (pinfunction "QH_7") (pintype "passive"))
      (node (ref "T4") (pin "5") (pinfunction "B1_5") (pintype "passive"))
    )
    (net (code "87") (name "Net-(SR2-GA)") (class "Default")
      (node (ref "SR2") (pin "15") (pinfunction "GA_15") (pintype "passive"))
      (node (ref "T5") (pin "2") (pinfunction "B2_2") (pintype "passive"))
    )
    (net (code "88") (name "Net-(SR2-QB)") (class "Default")
      (node (ref "SR2") (pin "1") (pinfunction "QB_1") (pintype "passive"))
      (node (ref "T5") (pin "5") (pinfunction "B1_5") (pintype "passive"))
    )
    (net (code "89") (name "Net-(SR2-QC)") (class "Default")
      (node (ref "SR2") (pin "2") (pinfunction "QC_2") (pintype "passive"))
      (node (ref "T6") (pin "2") (pinfunction "B2_2") (pintype "passive"))
    )
    (net (code "90") (name "Net-(SR2-QD)") (class "Default")
      (node (ref "SR2") (pin "3") (pinfunction "QD_3") (pintype "passive"))
      (node (ref "T6") (pin "5") (pinfunction "B1_5") (pintype "passive"))
    )
    (net (code "91") (name "Net-(SR2-QE)") (class "Default")
      (node (ref "SR2") (pin "4") (pinfunction "QE_4") (pintype "passive"))
      (node (ref "T7") (pin "2") (pinfunction "B2_2") (pintype "passive"))
    )
    (net (code "92") (name "Net-(SR2-QF)") (class "Default")
      (node (ref "SR2") (pin "5") (pinfunction "QF_5") (pintype "passive"))
      (node (ref "T7") (pin "5") (pinfunction "B1_5") (pintype "passive"))
    )
    (net (code "93") (name "Net-(SR2-QG)") (class "Default")
      (node (ref "SR2") (pin "6") (pinfunction "QG_6") (pintype "passive"))
      (node (ref "T8") (pin "2") (pinfunction "B2_2") (pintype "passive"))
    )
    (net (code "94") (name "Net-(SR2-QH')") (class "Default")
      (node (ref "SR2") (pin "9") (pinfunction "QH'_9") (pintype "passive"))
      (node (ref "SR3") (pin "14") (pinfunction "SER_14") (pintype "passive"))
    )
    (net (code "95") (name "Net-(SR2-QH)") (class "Default")
      (node (ref "SR2") (pin "7") (pinfunction "QH_7") (pintype "passive"))
      (node (ref "T8") (pin "5") (pinfunction "B1_5") (pintype "passive"))
    )
    (net (code "96") (name "Net-(SR3-GA)") (class "Default")
      (node (ref "SR3") (pin "15") (pinfunction "GA_15") (pintype "passive"))
      (node (ref "T9") (pin "2") (pinfunction "B2_2") (pintype "passive"))
    )
    (net (code "97") (name "Net-(SR3-QB)") (class "Default")
      (node (ref "SR3") (pin "1") (pinfunction "QB_1") (pintype "passive"))
      (node (ref "T9") (pin "5") (pinfunction "B1_5") (pintype "passive"))
    )
    (net (code "98") (name "Net-(SR3-QC)") (class "Default")
      (node (ref "SR3") (pin "2") (pinfunction "QC_2") (pintype "passive"))
      (node (ref "T10") (pin "2") (pinfunction "B2_2") (pintype "passive"))
    )
    (net (code "99") (name "Net-(SR3-QD)") (class "Default")
      (node (ref "SR3") (pin "3") (pinfunction "QD_3") (pintype "passive"))
      (node (ref "T10") (pin "5") (pinfunction "B1_5") (pintype "passive"))
    )
    (net (code "100") (name "Net-(SR3-QE)") (class "Default")
      (node (ref "SR3") (pin "4") (pinfunction "QE_4") (pintype "passive"))
      (node (ref "T11") (pin "2") (pinfunction "B2_2") (pintype "passive"))
    )
    (net (code "101") (name "Net-(SR3-QF)") (class "Default")
      (node (ref "SR3") (pin "5") (pinfunction "QF_5") (pintype "passive"))
      (node (ref "T11") (pin "5") (pinfunction "B1_5") (pintype "passive"))
    )
    (net (code "102") (name "Net-(SR3-QG)") (class "Default")
      (node (ref "SR3") (pin "6") (pinfunction "QG_6") (pintype "passive"))
      (node (ref "T12") (pin "2") (pinfunction "B2_2") (pintype "passive"))
    )
    (net (code "103") (name "Net-(SR3-QH')") (class "Default")
      (node (ref "SR3") (pin "9") (pinfunction "QH'_9") (pintype "passive"))
      (node (ref "SR4") (pin "14") (pinfunction "SER_14") (pintype "passive"))
    )
    (net (code "104") (name "Net-(SR3-QH)") (class "Default")
      (node (ref "SR3") (pin "7") (pinfunction "QH_7") (pintype "passive"))
      (node (ref "T12") (pin "5") (pinfunction "B1_5") (pintype "passive"))
    )
    (net (code "105") (name "Net-(SR4-GA)") (class "Default")
      (node (ref "SR4") (pin "15") (pinfunction "GA_15") (pintype "passive"))
      (node (ref "T13") (pin "2") (pinfunction "B2_2") (pintype "passive"))
    )
    (net (code "106") (name "Net-(SR4-QB)") (class "Default")
      (node (ref "SR4") (pin "1") (pinfunction "QB_1") (pintype "passive"))
      (node (ref "T13") (pin "5") (pinfunction "B1_5") (pintype "passive"))
    )
    (net (code "107") (name "Net-(SR4-QC)") (class "Default")
      (node (ref "SR4") (pin "2") (pinfunction "QC_2") (pintype "passive"))
      (node (ref "T14") (pin "2") (pinfunction "B2_2") (pintype "passive"))
    )
    (net (code "108") (name "Net-(SR4-QD)") (class "Default")
      (node (ref "SR4") (pin "3") (pinfunction "QD_3") (pintype "passive"))
      (node (ref "T14") (pin "5") (pinfunction "B1_5") (pintype "passive"))
    )
    (net (code "109") (name "Net-(SR4-QE)") (class "Default")
      (node (ref "SR4") (pin "4") (pinfunction "QE_4") (pintype "passive"))
      (node (ref "T15") (pin "2") (pinfunction "B2_2") (pintype "passive"))
    )
    (net (code "110") (name "Net-(SR4-QF)") (class "Default")
      (node (ref "SR4") (pin "5") (pinfunction "QF_5") (pintype "passive"))
      (node (ref "T15") (pin "5") (pinfunction "B1_5") (pintype "passive"))
    )
    (net (code "111") (name "Net-(SR4-QG)") (class "Default")
      (node (ref "SR4") (pin "6") (pinfunction "QG_6") (pintype "passive"))
      (node (ref "T16") (pin "2") (pinfunction "B2_2") (pintype "passive"))
    )
    (net (code "112") (name "Net-(SR4-QH')") (class "Default")
      (node (ref "SR4") (pin "9") (pinfunction "QH'_9") (pintype "passive"))
      (node (ref "SR5") (pin "14") (pinfunction "SER_14") (pintype "passive"))
    )
    (net (code "113") (name "Net-(SR4-QH)") (class "Default")
      (node (ref "SR4") (pin "7") (pinfunction "QH_7") (pintype "passive"))
      (node (ref "T16") (pin "5") (pinfunction "B1_5") (pintype "passive"))
    )
    (net (code "114") (name "Net-(SR5-GA)") (class "Default")
      (node (ref "SR5") (pin "15") (pinfunction "GA_15") (pintype "passive"))
      (node (ref "T17") (pin "2") (pinfunction "B2_2") (pintype "passive"))
    )
    (net (code "115") (name "Net-(SR5-QB)") (class "Default")
      (node (ref "SR5") (pin "1") (pinfunction "QB_1") (pintype "passive"))
      (node (ref "T17") (pin "5") (pinfunction "B1_5") (pintype "passive"))
    )
    (net (code "116") (name "Net-(SR5-QC)") (class "Default")
      (node (ref "SR5") (pin "2") (pinfunction "QC_2") (pintype "passive"))
      (node (ref "T18") (pin "2") (pinfunction "B2_2") (pintype "passive"))
    )
    (net (code "117") (name "Net-(SR5-QD)") (class "Default")
      (node (ref "SR5") (pin "3") (pinfunction "QD_3") (pintype "passive"))
      (node (ref "T18") (pin "5") (pinfunction "B1_5") (pintype "passive"))
    )
    (net (code "118") (name "Net-(SR5-QE)") (class "Default")
      (node (ref "SR5") (pin "4") (pinfunction "QE_4") (pintype "passive"))
      (node (ref "T19") (pin "2") (pinfunction "B2_2") (pintype "passive"))
    )
    (net (code "119") (name "Net-(SR5-QF)") (class "Default")
      (node (ref "SR5") (pin "5") (pinfunction "QF_5") (pintype "passive"))
      (node (ref "T19") (pin "5") (pinfunction "B1_5") (pintype "passive"))
    )
    (net (code "120") (name "Net-(SR5-QG)") (class "Default")
      (node (ref "SR5") (pin "6") (pinfunction "QG_6") (pintype "passive"))
      (node (ref "T20") (pin "2") (pinfunction "B2_2") (pintype "passive"))
    )
    (net (code "121") (name "Net-(SR5-QH')") (class "Default")
      (node (ref "SR5") (pin "9") (pinfunction "QH'_9") (pintype "passive"))
      (node (ref "SR6") (pin "14") (pinfunction "SER_14") (pintype "passive"))
    )
    (net (code "122") (name "Net-(SR5-QH)") (class "Default")
      (node (ref "SR5") (pin "7") (pinfunction "QH_7") (pintype "passive"))
      (node (ref "T20") (pin "5") (pinfunction "B1_5") (pintype "passive"))
    )
    (net (code "123") (name "Net-(SR6-GA)") (class "Default")
      (node (ref "SR6") (pin "15") (pinfunction "GA_15") (pintype "passive"))
      (node (ref "T21") (pin "2") (pinfunction "B2_2") (pintype "passive"))
    )
    (net (code "124") (name "Net-(SR6-QB)") (class "Default")
      (node (ref "SR6") (pin "1") (pinfunction "QB_1") (pintype "passive"))
      (node (ref "T21") (pin "5") (pinfunction "B1_5") (pintype "passive"))
    )
    (net (code "125") (name "Net-(SR6-QC)") (class "Default")
      (node (ref "SR6") (pin "2") (pinfunction "QC_2") (pintype "passive"))
      (node (ref "T22") (pin "2") (pinfunction "B2_2") (pintype "passive"))
    )
    (net (code "126") (name "Net-(SR6-QD)") (class "Default")
      (node (ref "SR6") (pin "3") (pinfunction "QD_3") (pintype "passive"))
      (node (ref "T22") (pin "5") (pinfunction "B1_5") (pintype "passive"))
    )
    (net (code "127") (name "Net-(SR6-QE)") (class "Default")
      (node (ref "SR6") (pin "4") (pinfunction "QE_4") (pintype "passive"))
      (node (ref "T23") (pin "2") (pinfunction "B2_2") (pintype "passive"))
    )
    (net (code "128") (name "Net-(SR6-QF)") (class "Default")
      (node (ref "SR6") (pin "5") (pinfunction "QF_5") (pintype "passive"))
      (node (ref "T23") (pin "5") (pinfunction "B1_5") (pintype "passive"))
    )
    (net (code "129") (name "Net-(SR6-QG)") (class "Default")
      (node (ref "SR6") (pin "6") (pinfunction "QG_6") (pintype "passive"))
      (node (ref "T24") (pin "2") (pinfunction "B2_2") (pintype "passive"))
    )
    (net (code "130") (name "Net-(SR6-QH')") (class "Default")
      (node (ref "SR6") (pin "9") (pinfunction "QH'_9") (pintype "passive"))
      (node (ref "SR7") (pin "14") (pinfunction "SER_14") (pintype "passive"))
    )
    (net (code "131") (name "Net-(SR6-QH)") (class "Default")
      (node (ref "SR6") (pin "7") (pinfunction "QH_7") (pintype "passive"))
      (node (ref "T24") (pin "5") (pinfunction "B1_5") (pintype "passive"))
    )
    (net (code "132") (name "Net-(SR7-GA)") (class "Default")
      (node (ref "SR7") (pin "15") (pinfunction "GA_15") (pintype "passive"))
      (node (ref "T25") (pin "2") (pinfunction "B2_2") (pintype "passive"))
    )
    (net (code "133") (name "Net-(SR7-QB)") (class "Default")
      (node (ref "SR7") (pin "1") (pinfunction "QB_1") (pintype "passive"))
      (node (ref "T25") (pin "5") (pinfunction "B1_5") (pintype "passive"))
    )
    (net (code "134") (name "Net-(SR7-QC)") (class "Default")
      (node (ref "SR7") (pin "2") (pinfunction "QC_2") (pintype "passive"))
      (node (ref "T26") (pin "2") (pinfunction "B2_2") (pintype "passive"))
    )
    (net (code "135") (name "Net-(SR7-QD)") (class "Default")
      (node (ref "SR7") (pin "3") (pinfunction "QD_3") (pintype "passive"))
      (node (ref "T26") (pin "5") (pinfunction "B1_5") (pintype "passive"))
    )
    (net (code "136") (name "Net-(SR7-QE)") (class "Default")
      (node (ref "SR7") (pin "4") (pinfunction "QE_4") (pintype "passive"))
      (node (ref "T27") (pin "2") (pinfunction "B2_2") (pintype "passive"))
    )
    (net (code "137") (name "Net-(SR7-QF)") (class "Default")
      (node (ref "SR7") (pin "5") (pinfunction "QF_5") (pintype "passive"))
      (node (ref "T27") (pin "5") (pinfunction "B1_5") (pintype "passive"))
    )
    (net (code "138") (name "Net-(SR7-QG)") (class "Default")
      (node (ref "SR7") (pin "6") (pinfunction "QG_6") (pintype "passive"))
      (node (ref "T28") (pin "2") (pinfunction "B2_2") (pintype "passive"))
    )
    (net (code "139") (name "Net-(SR7-QH')") (class "Default")
      (node (ref "SR7") (pin "9") (pinfunction "QH'_9") (pintype "passive"))
      (node (ref "SR8") (pin "14") (pinfunction "SER_14") (pintype "passive"))
    )
    (net (code "140") (name "Net-(SR7-QH)") (class "Default")
      (node (ref "SR7") (pin "7") (pinfunction "QH_7") (pintype "passive"))
      (node (ref "T28") (pin "5") (pinfunction "B1_5") (pintype "passive"))
    )
    (net (code "141") (name "Net-(SR8-GA)") (class "Default")
      (node (ref "SR8") (pin "15") (pinfunction "GA_15") (pintype "passive"))
      (node (ref "T29") (pin "2") (pinfunction "B2_2") (pintype "passive"))
    )
    (net (code "142") (name "Net-(SR8-QB)") (class "Default")
      (node (ref "SR8") (pin "1") (pinfunction "QB_1") (pintype "passive"))
      (node (ref "T29") (pin "5") (pinfunction "B1_5") (pintype "passive"))
    )
    (net (code "143") (name "Net-(SR8-QC)") (class "Default")
      (node (ref "SR8") (pin "2") (pinfunction "QC_2") (pintype "passive"))
      (node (ref "T30") (pin "2") (pinfunction "B2_2") (pintype "passive"))
    )
    (net (code "144") (name "Net-(SR8-QD)") (class "Default")
      (node (ref "SR8") (pin "3") (pinfunction "QD_3") (pintype "passive"))
      (node (ref "T30") (pin "5") (pinfunction "B1_5") (pintype "passive"))
    )
    (net (code "145") (name "unconnected-(Header1-Pad1)") (class "Default")
      (node (ref "Header1") (pin "1") (pinfunction "1_1") (pintype "passive"))
    )
    (net (code "146") (name "unconnected-(Header1-Pad5)") (class "Default")
      (node (ref "Header1") (pin "5") (pinfunction "5_5") (pintype "passive"))
    )
    (net (code "147") (name "unconnected-(IC2-ADC-Pad2)") (class "Default")
      (node (ref "IC2") (pin "2") (pinfunction "ADC_2") (pintype "passive"))
    )
    (net (code "148") (name "unconnected-(IC2-CSO-Pad9)") (class "Default")
      (node (ref "IC2") (pin "9") (pinfunction "CSO_9") (pintype "passive"))
    )
    (net (code "149") (name "unconnected-(IC2-EN-Pad3)") (class "Default")
      (node (ref "IC2") (pin "3") (pinfunction "EN_3") (pintype "passive"))
    )
    (net (code "150") (name "unconnected-(IC2-GPIO0-Pad18)") (class "Default")
      (node (ref "IC2") (pin "18") (pinfunction "GPIO0_18") (pintype "passive"))
    )
    (net (code "151") (name "unconnected-(IC2-GPIO2-Pad17)") (class "Default")
      (node (ref "IC2") (pin "17") (pinfunction "GPIO2_17") (pintype "passive"))
    )
    (net (code "152") (name "unconnected-(IC2-GPIO9-Pad11)") (class "Default")
      (node (ref "IC2") (pin "11") (pinfunction "GPIO9_11") (pintype "passive"))
    )
    (net (code "153") (name "unconnected-(IC2-GPIO10-Pad12)") (class "Default")
      (node (ref "IC2") (pin "12") (pinfunction "GPIO10_12") (pintype "passive"))
    )
    (net (code "154") (name "unconnected-(IC2-GPIO13-Pad7)") (class "Default")
      (node (ref "IC2") (pin "7") (pinfunction "GPIO13_7") (pintype "passive"))
    )
    (net (code "155") (name "unconnected-(IC2-GPIO15-Pad16)") (class "Default")
      (node (ref "IC2") (pin "16") (pinfunction "GPIO15_16") (pintype "passive"))
    )
    (net (code "156") (name "unconnected-(IC2-MISO-Pad10)") (class "Default")
      (node (ref "IC2") (pin "10") (pinfunction "MISO_10") (pintype "passive"))
    )
    (net (code "157") (name "unconnected-(IC2-MOSI-Pad13)") (class "Default")
      (node (ref "IC2") (pin "13") (pinfunction "MOSI_13") (pintype "passive"))
    )
    (net (code "158") (name "unconnected-(IC2-RST-Pad1)") (class "Default")
      (node (ref "IC2") (pin "1") (pinfunction "RST_1") (pintype "passive"))
    )
    (net (code "159") (name "unconnected-(IC2-SCLK-Pad14)") (class "Default")
      (node (ref "IC2") (pin "14") (pinfunction "SCLK_14") (pintype "passive"))
    )
    (net (code "160") (name "unconnected-(IC3-32kHz-Pad1)") (class "Default")
      (node (ref "IC3") (pin "1") (pinfunction "32kHz_1") (pintype "open_collector"))
    )
    (net (code "161") (name "unconnected-(IC3-~{INT}{slash}SQW-Pad3)") (class "Default")
      (node (ref "IC3") (pin "3") (pinfunction "~{INT}/SQW_3") (pintype "open_collector"))
    )
    (net (code "162") (name "unconnected-(IC3-~{RST}-Pad4)") (class "Default")
      (node (ref "IC3") (pin "4") (pinfunction "~{RST}_4") (pintype "bidirectional"))
    )
    (net (code "163") (name "unconnected-(NX1-NC-Pad1)") (class "Default")
      (node (ref "NX1") (pin "1") (pinfunction "NC_1") (pintype "passive"))
    )
    (net (code "164") (name "unconnected-(NX1-NC-Pad8)") (class "Default")
      (node (ref "NX1") (pin "8") (pinfunction "NC_8") (pintype "passive"))
    )
    (net (code "165") (name "unconnected-(NX2-NC-Pad1)") (class "Default")
      (node (ref "NX2") (pin "1") (pinfunction "NC_1") (pintype "passive"))
    )
    (net (code "166") (name "unconnected-(NX2-NC-Pad8)") (class "Default")
      (node (ref "NX2") (pin "8") (pinfunction "NC_8") (pintype "passive"))
    )
    (net (code "167") (name "unconnected-(NX3-NC-Pad1)") (class "Default")
      (node (ref "NX3") (pin "1") (pinfunction "NC_1") (pintype "passive"))
    )
    (net (code "168") (name "unconnected-(NX3-NC-Pad8)") (class "Default")
      (node (ref "NX3") (pin "8") (pinfunction "NC_8") (pintype "passive"))
    )
    (net (code "169") (name "unconnected-(NX4-NC-Pad1)") (class "Default")
      (node (ref "NX4") (pin "1") (pinfunction "NC_1") (pintype "passive"))
    )
    (net (code "170") (name "unconnected-(NX4-NC-Pad8)") (class "Default")
      (node (ref "NX4") (pin "8") (pinfunction "NC_8") (pintype "passive"))
    )
    (net (code "171") (name "unconnected-(NX5-NC-Pad1)") (class "Default")
      (node (ref "NX5") (pin "1") (pinfunction "NC_1") (pintype "passive"))
    )
    (net (code "172") (name "unconnected-(NX5-NC-Pad8)") (class "Default")
      (node (ref "NX5") (pin "8") (pinfunction "NC_8") (pintype "passive"))
    )
    (net (code "173") (name "unconnected-(NX6-NC-Pad1)") (class "Default")
      (node (ref "NX6") (pin "1") (pinfunction "NC_1") (pintype "passive"))
    )
    (net (code "174") (name "unconnected-(NX6-NC-Pad8)") (class "Default")
      (node (ref "NX6") (pin "8") (pinfunction "NC_8") (pintype "passive"))
    )
    (net (code "175") (name "unconnected-(SR8-QE-Pad4)") (class "Default")
      (node (ref "SR8") (pin "4") (pinfunction "QE_4") (pintype "passive"))
    )
    (net (code "176") (name "unconnected-(SR8-QF-Pad5)") (class "Default")
      (node (ref "SR8") (pin "5") (pinfunction "QF_5") (pintype "passive"))
    )
    (net (code "177") (name "unconnected-(SR8-QG-Pad6)") (class "Default")
      (node (ref "SR8") (pin "6") (pinfunction "QG_6") (pintype "passive"))
    )
    (net (code "178") (name "unconnected-(SR8-QH'-Pad9)") (class "Default")
      (node (ref "SR8") (pin "9") (pinfunction "QH'_9") (pintype "passive"))
    )
    (net (code "179") (name "unconnected-(SR8-QH-Pad7)") (class "Default")
      (node (ref "SR8") (pin "7") (pinfunction "QH_7") (pintype "passive"))
    )
  )
)
